# integratedBertha.net
KiCad netlist of a schematic drawn in EAGLE
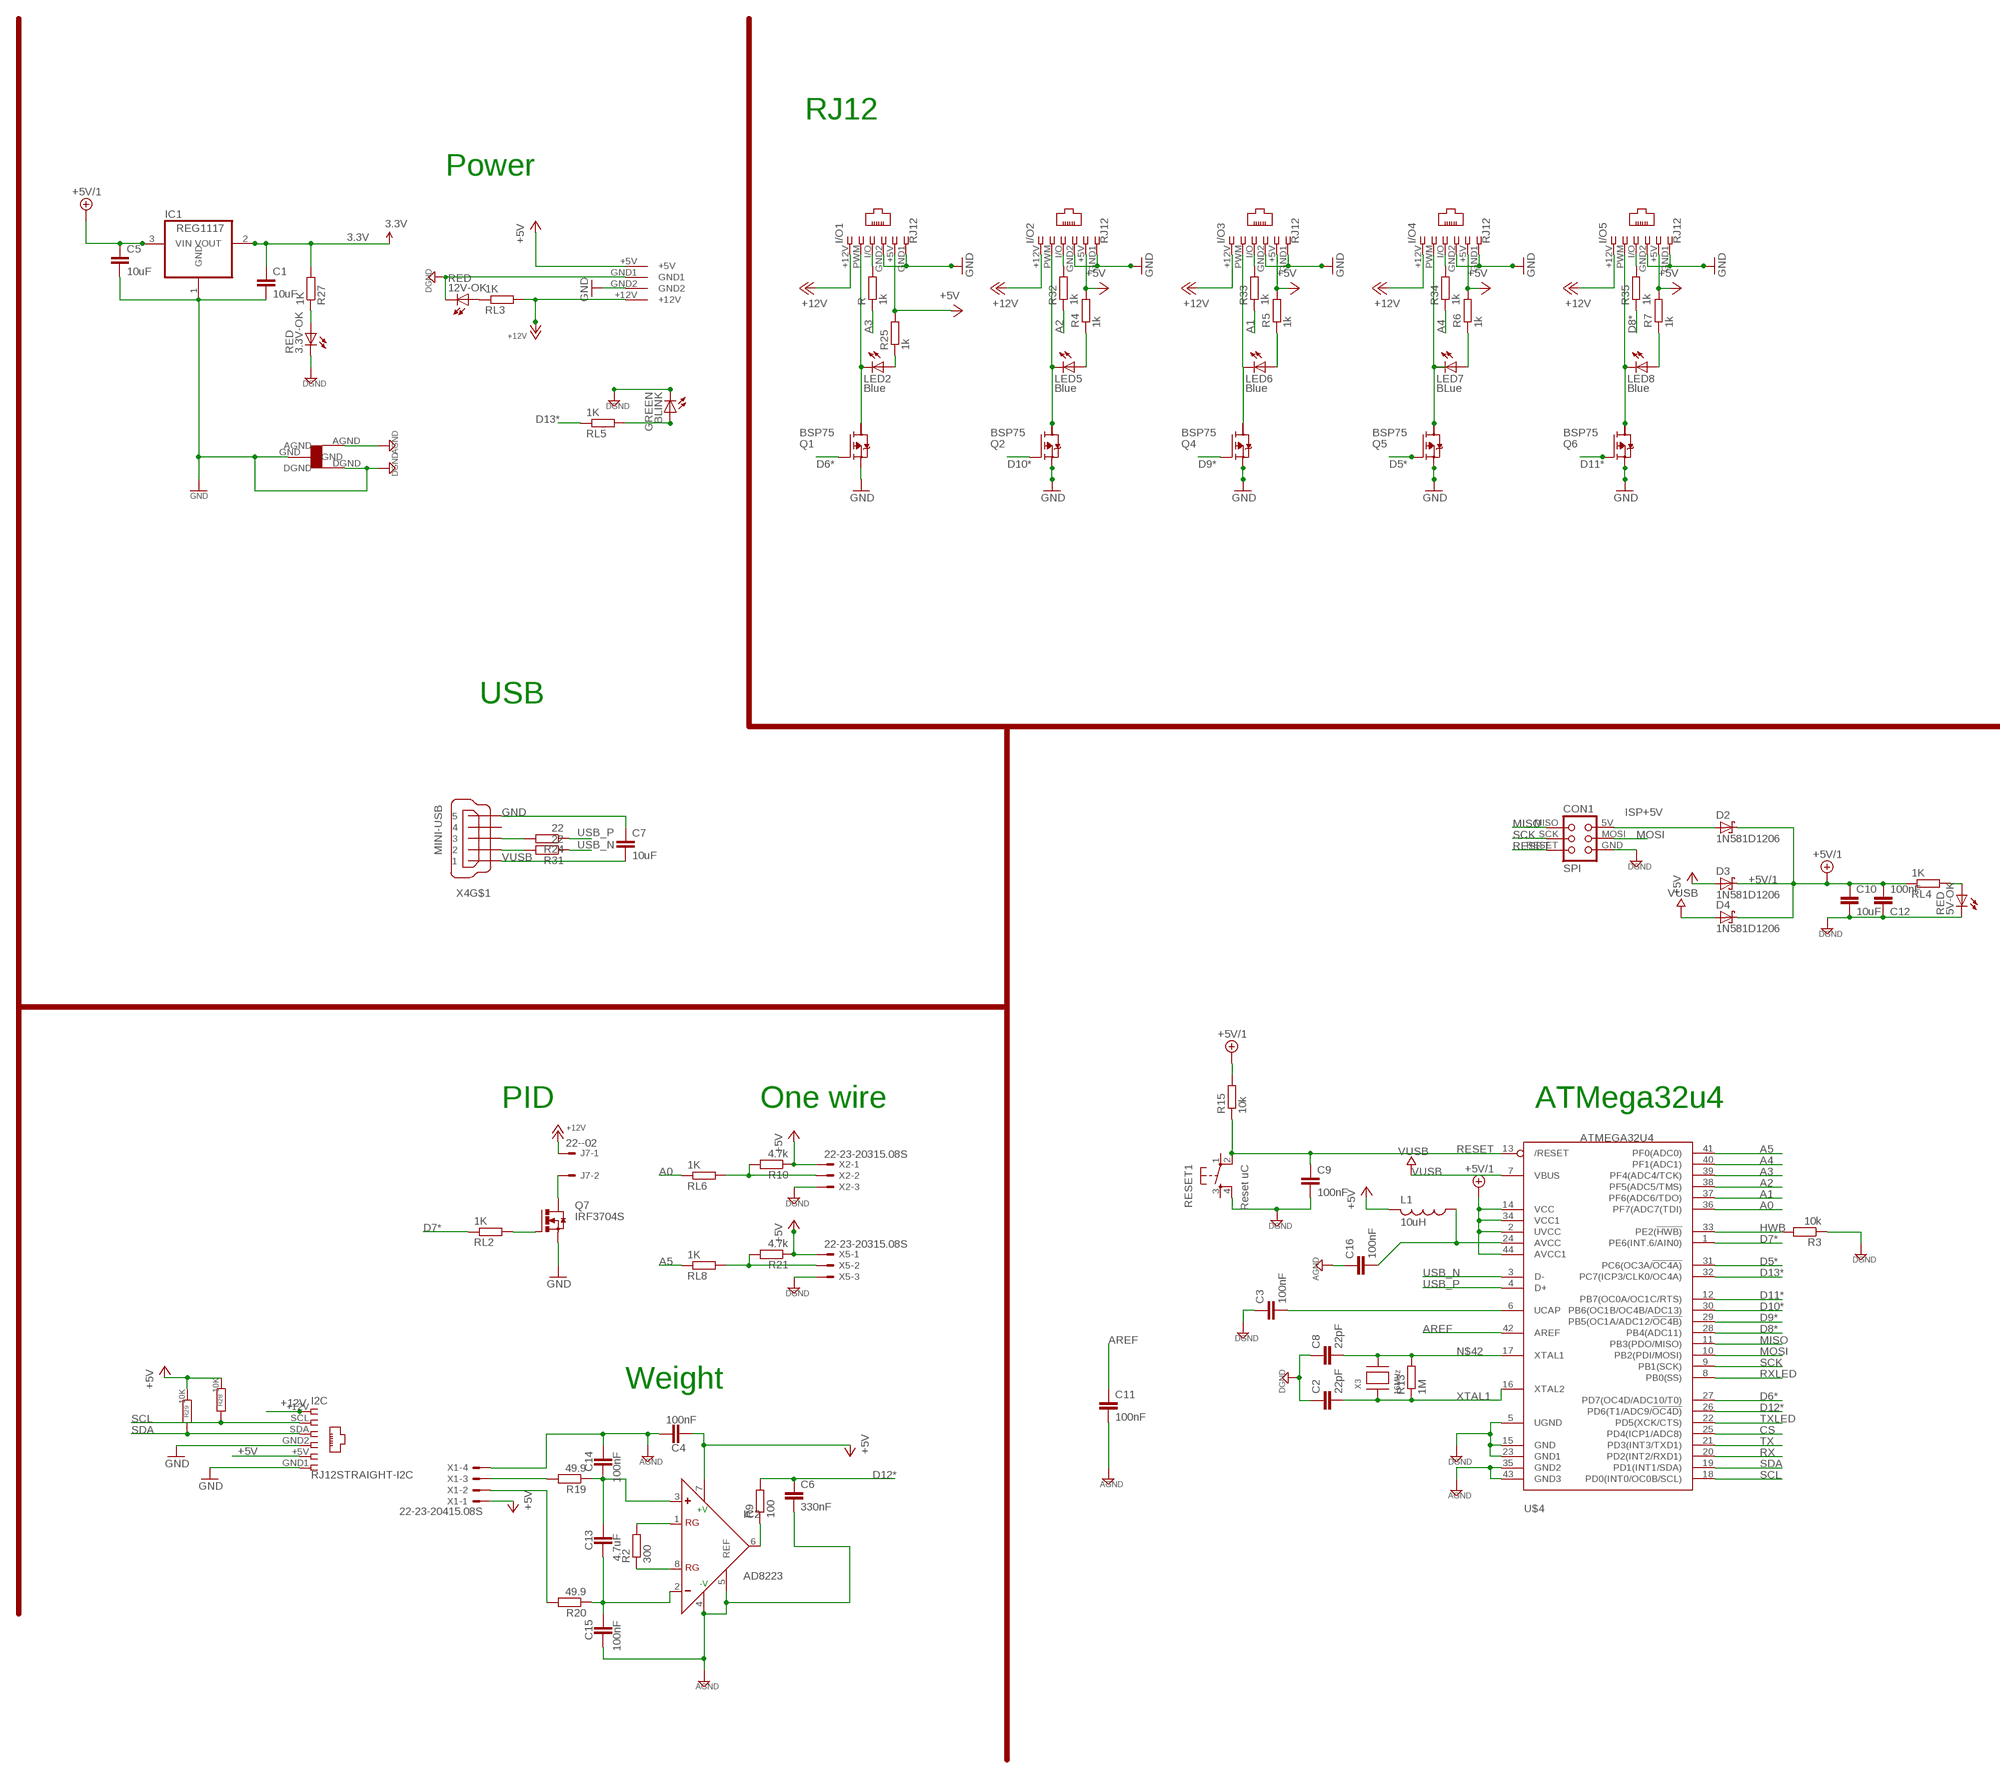
[diagram p0: schematic, sheet 1, part 1 of 2]
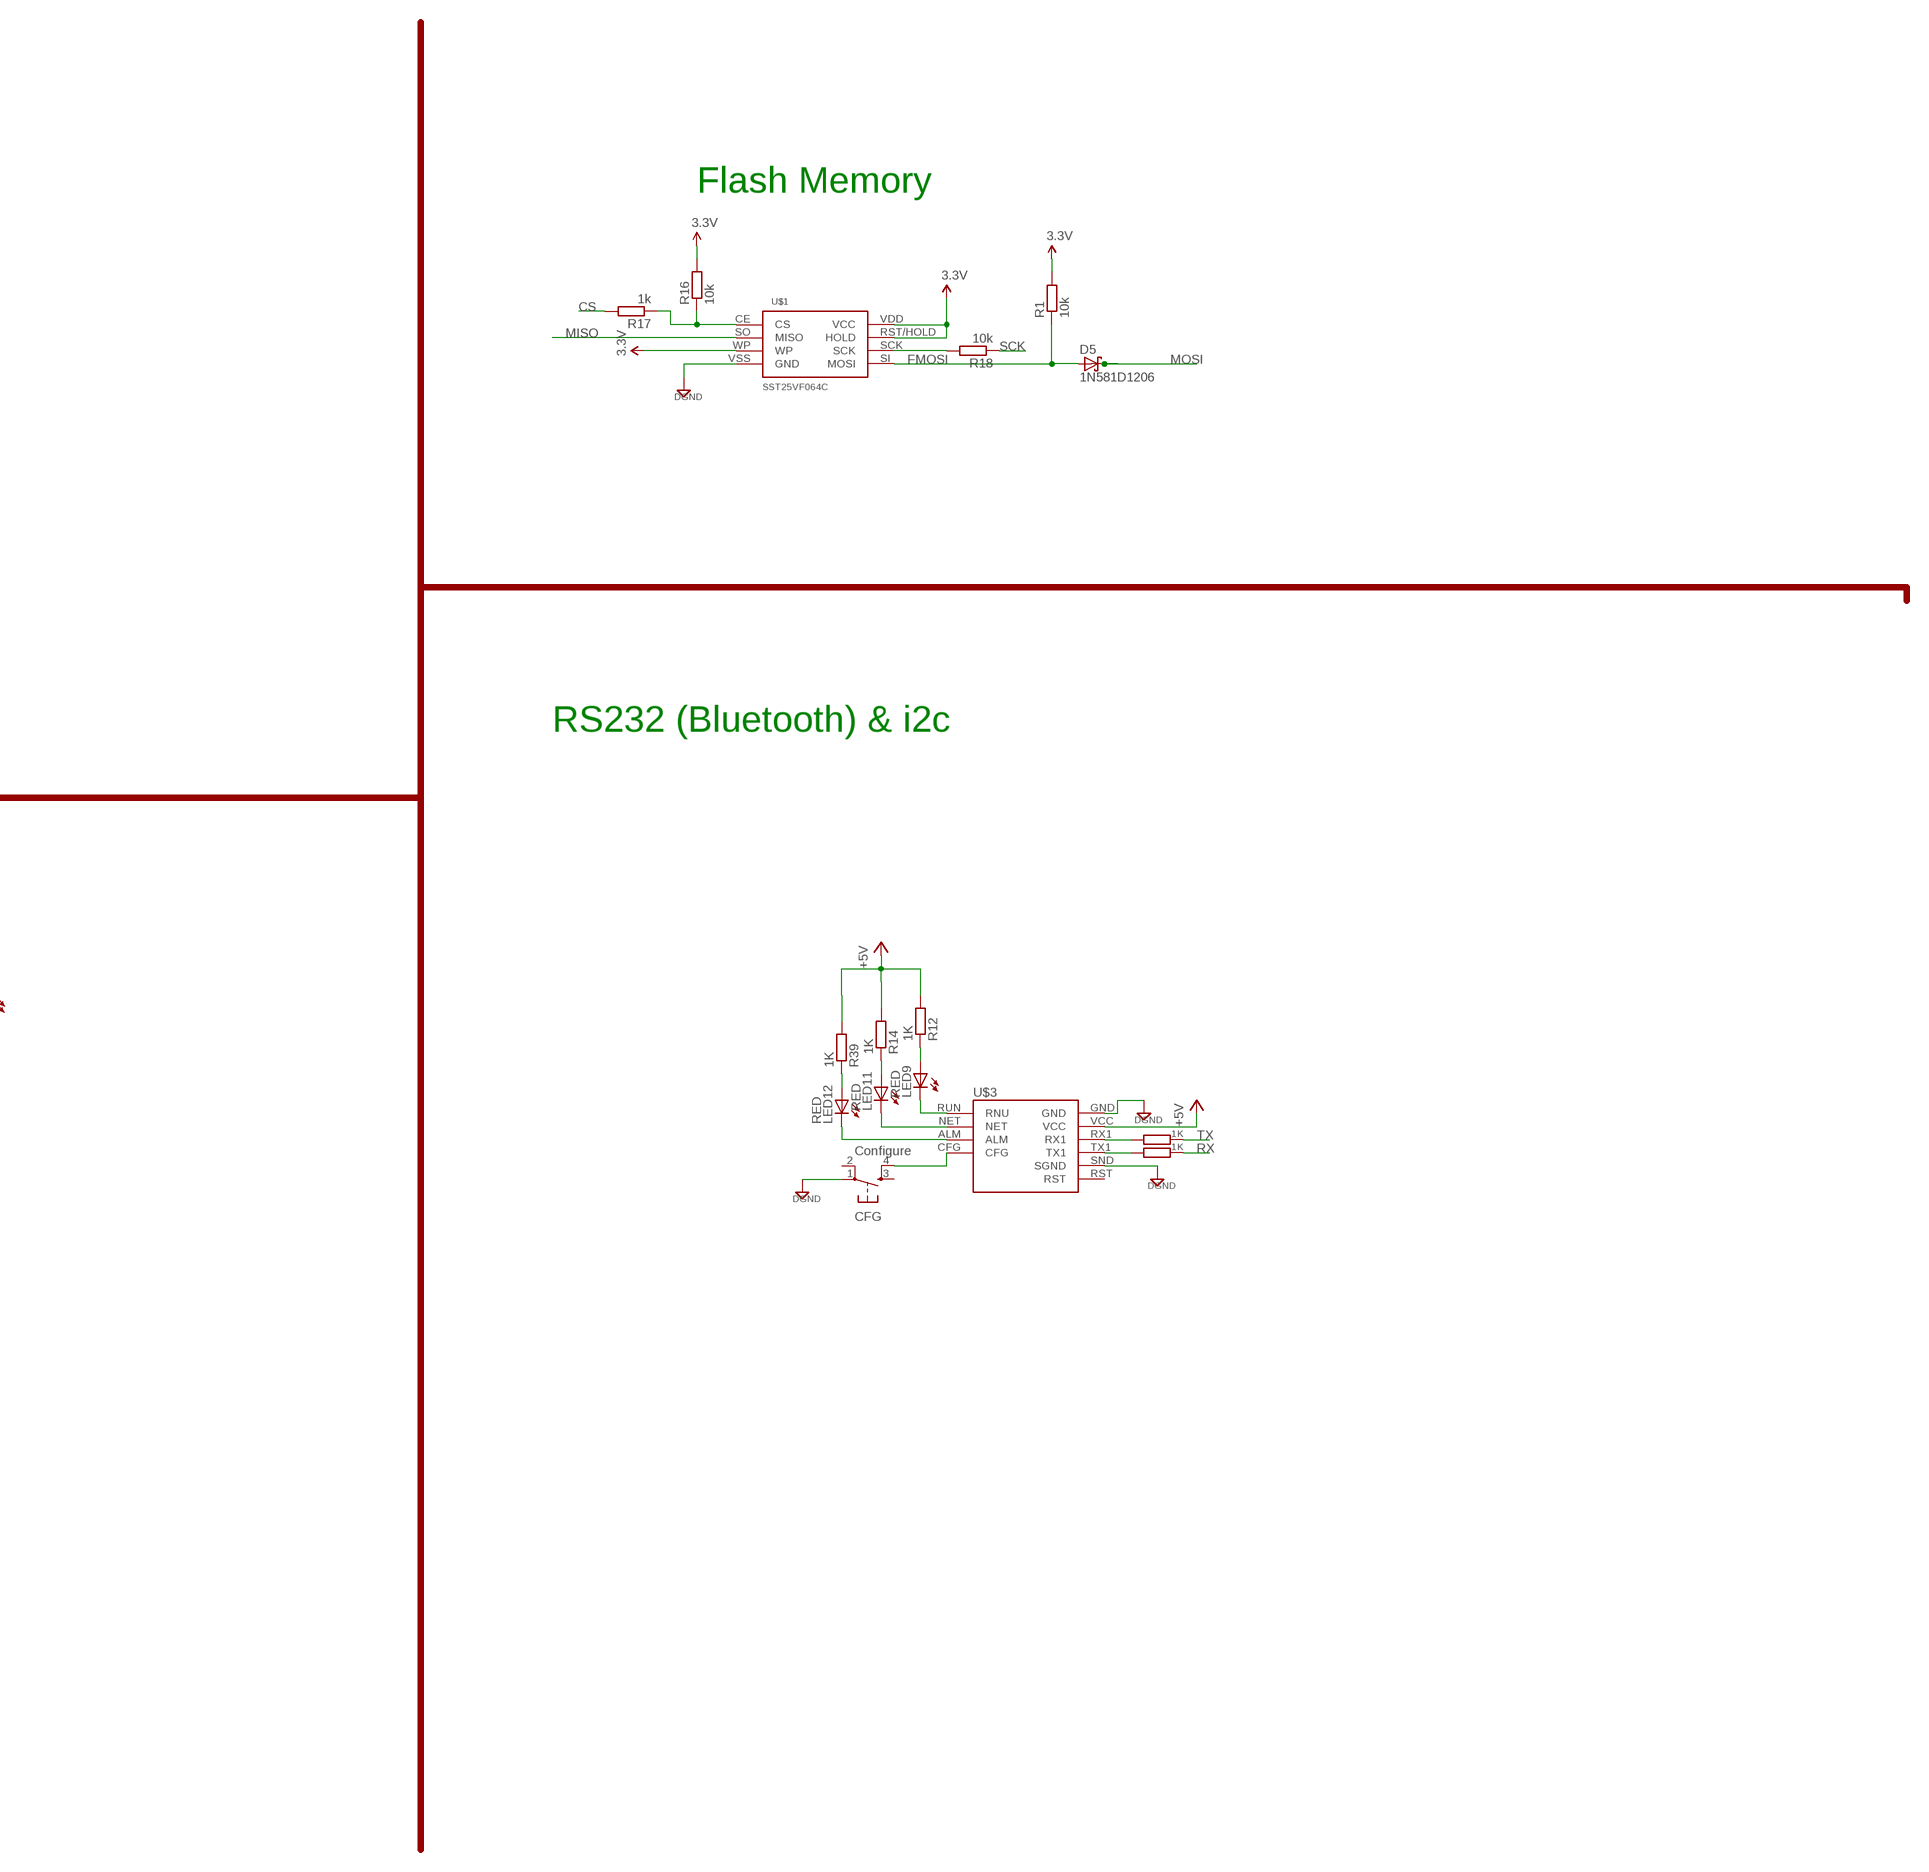
[diagram p1: schematic, sheet 1, part 2 of 2]

(export (version "E")
  (design (tool "Eeschema 10.0.6"))
  (components
    (comp (ref "3.3V-OK")
      (value "RED")
      (footprint "eagle-import:CHIPLED_1206")
      (libsource (lib "eagle-import") (part "LEDCHIPLED_1206"))
    )
    (comp (ref "5V-OK")
      (value "RED")
      (footprint "eagle-import:CHIPLED_1206")
      (libsource (lib "eagle-import") (part "LEDCHIPLED_1206"))
    )
    (comp (ref "12V-OK")
      (value "RED")
      (footprint "eagle-import:CHIPLED_1206")
      (libsource (lib "eagle-import") (part "LEDCHIPLED_1206"))
    )
    (comp (ref "BLINK")
      (value "GREEN")
      (footprint "eagle-import:CHIPLED_1206")
      (libsource (lib "eagle-import") (part "LEDCHIPLED_1206"))
    )
    (comp (ref "C1")
      (value "10uF")
      (footprint "eagle-import:C1206")
      (libsource (lib "eagle-import") (part "C-EUC1206"))
    )
    (comp (ref "C2")
      (value "22pF")
      (footprint "eagle-import:C1206")
      (libsource (lib "eagle-import") (part "C-EUC1206"))
    )
    (comp (ref "C3")
      (value "100nF")
      (footprint "eagle-import:C1206")
      (libsource (lib "eagle-import") (part "C-EUC1206"))
    )
    (comp (ref "C4")
      (value "100nF")
      (footprint "eagle-import:C1206")
      (libsource (lib "eagle-import") (part "C-EUC1206"))
    )
    (comp (ref "C5")
      (value "10uF")
      (footprint "eagle-import:C1206")
      (libsource (lib "eagle-import") (part "C-EUC1206"))
    )
    (comp (ref "C6")
      (value "330nF")
      (footprint "eagle-import:C1206")
      (libsource (lib "eagle-import") (part "C-EUC1206"))
    )
    (comp (ref "C7")
      (value "10uF")
      (footprint "eagle-import:C1206")
      (libsource (lib "eagle-import") (part "C-EUC1206"))
    )
    (comp (ref "C8")
      (value "22pF")
      (footprint "eagle-import:C1206")
      (libsource (lib "eagle-import") (part "C-EUC1206"))
    )
    (comp (ref "C9")
      (value "100nF")
      (footprint "eagle-import:C1206")
      (libsource (lib "eagle-import") (part "C-EUC1206"))
    )
    (comp (ref "C10")
      (value "10uF")
      (footprint "eagle-import:C1206")
      (libsource (lib "eagle-import") (part "C-EUC1206"))
    )
    (comp (ref "C11")
      (value "100nF")
      (footprint "eagle-import:C1206")
      (libsource (lib "eagle-import") (part "C-EUC1206"))
    )
    (comp (ref "C12")
      (value "100nF")
      (footprint "eagle-import:C1206")
      (libsource (lib "eagle-import") (part "C-EUC1206"))
    )
    (comp (ref "C13")
      (value "4.7uF")
      (footprint "eagle-import:C1206")
      (libsource (lib "eagle-import") (part "C-EUC1206"))
    )
    (comp (ref "C14")
      (value "100nF")
      (footprint "eagle-import:C1206")
      (libsource (lib "eagle-import") (part "C-EUC1206"))
    )
    (comp (ref "C15")
      (value "100nF")
      (footprint "eagle-import:C1206")
      (libsource (lib "eagle-import") (part "C-EUC1206"))
    )
    (comp (ref "C16")
      (value "100nF")
      (footprint "eagle-import:C1206")
      (libsource (lib "eagle-import") (part "C-EUC1206"))
    )
    (comp (ref "CFG")
      (value "Configure")
      (footprint "eagle-import:TACTILE_SWITCH_SMD")
      (libsource (lib "eagle-import") (part "TAC_SWITCHSMD"))
    )
    (comp (ref "CON1")
      (value "SPI")
      (footprint "eagle-import:TC2030-MCP-NL")
      (libsource (lib "eagle-import") (part "TINYISPT"))
    )
    (comp (ref "D2")
      (value "1N581D1206")
      (footprint "eagle-import:LED-1206")
      (libsource (lib "eagle-import") (part "1N581D1206"))
    )
    (comp (ref "D3")
      (value "1N581D1206")
      (footprint "eagle-import:LED-1206")
      (libsource (lib "eagle-import") (part "1N581D1206"))
    )
    (comp (ref "D4")
      (value "1N581D1206")
      (footprint "eagle-import:LED-1206")
      (libsource (lib "eagle-import") (part "1N581D1206"))
    )
    (comp (ref "D5")
      (value "1N581D1206")
      (footprint "eagle-import:LED-1206")
      (libsource (lib "eagle-import") (part "1N581D1206"))
    )
    (comp (ref "I/O1")
      (value "RJ12")
      (footprint "eagle-import:RJ12-STRAIGHT")
      (libsource (lib "eagle-import") (part "RJ12STRAIGHT"))
    )
    (comp (ref "I/O2")
      (value "RJ12")
      (footprint "eagle-import:RJ12-STRAIGHT")
      (libsource (lib "eagle-import") (part "RJ12STRAIGHT"))
    )
    (comp (ref "I/O3")
      (value "RJ12")
      (footprint "eagle-import:RJ12-STRAIGHT")
      (libsource (lib "eagle-import") (part "RJ12STRAIGHT"))
    )
    (comp (ref "I/O4")
      (value "RJ12")
      (footprint "eagle-import:RJ12-STRAIGHT")
      (libsource (lib "eagle-import") (part "RJ12STRAIGHT"))
    )
    (comp (ref "I/O5")
      (value "RJ12")
      (footprint "eagle-import:RJ12-STRAIGHT")
      (libsource (lib "eagle-import") (part "RJ12STRAIGHT"))
    )
    (comp (ref "I2C")
      (value "RJ12STRAIGHT-I2C")
      (footprint "eagle-import:RJ12-STRAIGHT-I2C")
      (libsource (lib "eagle-import") (part "RJ12STRAIGHT-I2C"))
    )
    (comp (ref "IC1")
      (value "REG1117")
      (footprint "eagle-import:SOT223")
      (libsource (lib "eagle-import") (part "REG1117"))
    )
    (comp (ref "IC2")
      (value "AD8223")
      (footprint "eagle-import:SO8")
      (fields (field (name "MPN") "AD620AR"))
      (libsource (lib "eagle-import") (part "AD620R"))
    )
    (comp (ref "J7")
      (value "22--02")
      (footprint "eagle-import:2-PIN-5.08S")
      (libsource (lib "eagle-import") (part "22-?-02"))
    )
    (comp (ref "L1")
      (value "10uH")
      (footprint "eagle-import:L2012C")
      (libsource (lib "eagle-import") (part "L-USL2012C"))
    )
    (comp (ref "LED2")
      (value "Blue")
      (footprint "eagle-import:CHIPLED_1206")
      (libsource (lib "eagle-import") (part "LEDCHIPLED_1206"))
    )
    (comp (ref "LED5")
      (value "Blue")
      (footprint "eagle-import:CHIPLED_1206")
      (libsource (lib "eagle-import") (part "LEDCHIPLED_1206"))
    )
    (comp (ref "LED6")
      (value "Blue")
      (footprint "eagle-import:CHIPLED_1206")
      (libsource (lib "eagle-import") (part "LEDCHIPLED_1206"))
    )
    (comp (ref "LED7")
      (value "BLue")
      (footprint "eagle-import:CHIPLED_1206")
      (libsource (lib "eagle-import") (part "LEDCHIPLED_1206"))
    )
    (comp (ref "LED8")
      (value "Blue")
      (footprint "eagle-import:CHIPLED_1206")
      (libsource (lib "eagle-import") (part "LEDCHIPLED_1206"))
    )
    (comp (ref "LED9")
      (value "RED")
      (footprint "eagle-import:CHIPLED_1206")
      (libsource (lib "eagle-import") (part "LEDCHIPLED_1206"))
    )
    (comp (ref "LED11")
      (value "RED")
      (footprint "eagle-import:CHIPLED_1206")
      (libsource (lib "eagle-import") (part "LEDCHIPLED_1206"))
    )
    (comp (ref "LED12")
      (value "RED")
      (footprint "eagle-import:CHIPLED_1206")
      (libsource (lib "eagle-import") (part "LEDCHIPLED_1206"))
    )
    (comp (ref "Q1")
      (value "BSP75")
      (footprint "eagle-import:PG-SOT-223")
      (libsource (lib "eagle-import") (part "BSP613P"))
    )
    (comp (ref "Q2")
      (value "BSP75")
      (footprint "eagle-import:PG-SOT-223")
      (libsource (lib "eagle-import") (part "BSP613P"))
    )
    (comp (ref "Q4")
      (value "BSP75")
      (footprint "eagle-import:PG-SOT-223")
      (libsource (lib "eagle-import") (part "BSP613P"))
    )
    (comp (ref "Q5")
      (value "BSP75")
      (footprint "eagle-import:PG-SOT-223")
      (libsource (lib "eagle-import") (part "BSP613P"))
    )
    (comp (ref "Q6")
      (value "BSP75")
      (footprint "eagle-import:PG-SOT-223")
      (libsource (lib "eagle-import") (part "BSP613P"))
    )
    (comp (ref "Q7")
      (value "IRF3704S")
      (footprint "eagle-import:D2PACK")
      (libsource (lib "eagle-import") (part "IRF3704S"))
    )
    (comp (ref "R")
      (value "1k")
      (footprint "eagle-import:R0805")
      (libsource (lib "eagle-import") (part "R-EU_R0805"))
    )
    (comp (ref "R1")
      (value "10k")
      (footprint "eagle-import:R0805")
      (libsource (lib "eagle-import") (part "R-EU_R0805"))
    )
    (comp (ref "R2")
      (value "300")
      (footprint "eagle-import:R1206")
      (libsource (lib "eagle-import") (part "resistor_R-EU_R1206"))
    )
    (comp (ref "R3")
      (value "10k")
      (footprint "eagle-import:M0805")
      (libsource (lib "eagle-import") (part "resistor_R-EU_M0805"))
    )
    (comp (ref "R4")
      (value "1k")
      (footprint "eagle-import:R0805")
      (libsource (lib "eagle-import") (part "R-EU_R0805"))
    )
    (comp (ref "R5")
      (value "1k")
      (footprint "eagle-import:R0805")
      (libsource (lib "eagle-import") (part "R-EU_R0805"))
    )
    (comp (ref "R6")
      (value "1k")
      (footprint "eagle-import:R0805")
      (libsource (lib "eagle-import") (part "R-EU_R0805"))
    )
    (comp (ref "R7")
      (value "1k")
      (footprint "eagle-import:R0805")
      (libsource (lib "eagle-import") (part "R-EU_R0805"))
    )
    (comp (ref "R8")
      (value "1K")
      (footprint "eagle-import:R0805")
      (libsource (lib "eagle-import") (part "R-EU_R0805"))
    )
    (comp (ref "R9")
      (value "100")
      (footprint "eagle-import:R1206")
      (libsource (lib "eagle-import") (part "resistor_R-EU_R1206"))
    )
    (comp (ref "R10")
      (value "4.7k")
      (footprint "eagle-import:R1206")
      (libsource (lib "eagle-import") (part "resistor_R-EU_R1206"))
    )
    (comp (ref "R11")
      (value "1K")
      (footprint "eagle-import:R0805")
      (libsource (lib "eagle-import") (part "R-EU_R0805"))
    )
    (comp (ref "R12")
      (value "1K")
      (footprint "eagle-import:R0805")
      (libsource (lib "eagle-import") (part "R-EU_R0805"))
    )
    (comp (ref "R13")
      (value "1M")
      (footprint "eagle-import:R1206")
      (libsource (lib "eagle-import") (part "R-EU_R1206"))
    )
    (comp (ref "R14")
      (value "1K")
      (footprint "eagle-import:R0805")
      (libsource (lib "eagle-import") (part "R-EU_R0805"))
    )
    (comp (ref "R15")
      (value "10k")
      (footprint "eagle-import:M0805")
      (libsource (lib "eagle-import") (part "resistor_R-EU_M0805"))
    )
    (comp (ref "R16")
      (value "10k")
      (footprint "eagle-import:R0805")
      (libsource (lib "eagle-import") (part "R-EU_R0805"))
    )
    (comp (ref "R17")
      (value "1k")
      (footprint "eagle-import:R0805")
      (libsource (lib "eagle-import") (part "R-EU_R0805"))
    )
    (comp (ref "R18")
      (value "10k")
      (footprint "eagle-import:R0805")
      (libsource (lib "eagle-import") (part "R-EU_R0805"))
    )
    (comp (ref "R19")
      (value "49.9")
      (footprint "eagle-import:R1206")
      (libsource (lib "eagle-import") (part "resistor_R-EU_R1206"))
    )
    (comp (ref "R20")
      (value "49.9")
      (footprint "eagle-import:R1206")
      (libsource (lib "eagle-import") (part "resistor_R-EU_R1206"))
    )
    (comp (ref "R21")
      (value "4.7k")
      (footprint "eagle-import:R1206")
      (libsource (lib "eagle-import") (part "resistor_R-EU_R1206"))
    )
    (comp (ref "R24")
      (value "22")
      (footprint "eagle-import:M1206")
      (libsource (lib "eagle-import") (part "resistor_R-EU_M1206"))
    )
    (comp (ref "R25")
      (value "1k")
      (footprint "eagle-import:R0805")
      (libsource (lib "eagle-import") (part "R-EU_R0805"))
    )
    (comp (ref "R27")
      (value "1K")
      (footprint "eagle-import:R0805")
      (libsource (lib "eagle-import") (part "R-EU_R0805"))
    )
    (comp (ref "R28")
      (value "10K")
      (footprint "eagle-import:M0805")
      (libsource (lib "eagle-import") (part "resistor_R-EU_M0805"))
    )
    (comp (ref "R29")
      (value "10K")
      (footprint "eagle-import:M0805")
      (libsource (lib "eagle-import") (part "resistor_R-EU_M0805"))
    )
    (comp (ref "R31")
      (value "22")
      (footprint "eagle-import:M1206")
      (libsource (lib "eagle-import") (part "resistor_R-EU_M1206"))
    )
    (comp (ref "R32")
      (value "1k")
      (footprint "eagle-import:R0805")
      (libsource (lib "eagle-import") (part "R-EU_R0805"))
    )
    (comp (ref "R33")
      (value "1k")
      (footprint "eagle-import:R0805")
      (libsource (lib "eagle-import") (part "R-EU_R0805"))
    )
    (comp (ref "R34")
      (value "1k")
      (footprint "eagle-import:R0805")
      (libsource (lib "eagle-import") (part "R-EU_R0805"))
    )
    (comp (ref "R35")
      (value "1k")
      (footprint "eagle-import:R0805")
      (libsource (lib "eagle-import") (part "R-EU_R0805"))
    )
    (comp (ref "R39")
      (value "1K")
      (footprint "eagle-import:R0805")
      (libsource (lib "eagle-import") (part "R-EU_R0805"))
    )
    (comp (ref "RESET1")
      (value "Reset uC")
      (footprint "eagle-import:TACTILE_SWITCH_SMD")
      (libsource (lib "eagle-import") (part "TAC_SWITCHSMD"))
    )
    (comp (ref "RL2")
      (value "1K")
      (footprint "eagle-import:R0805")
      (libsource (lib "eagle-import") (part "R-EU_R0805"))
    )
    (comp (ref "RL3")
      (value "1K")
      (footprint "eagle-import:R0805")
      (libsource (lib "eagle-import") (part "R-EU_R0805"))
    )
    (comp (ref "RL4")
      (value "1K")
      (footprint "eagle-import:R0805")
      (libsource (lib "eagle-import") (part "resistor_R-EU_R0805"))
    )
    (comp (ref "RL5")
      (value "1K")
      (footprint "eagle-import:R0805")
      (libsource (lib "eagle-import") (part "R-EU_R0805"))
    )
    (comp (ref "RL6")
      (value "1K")
      (footprint "eagle-import:R0805")
      (libsource (lib "eagle-import") (part "R-EU_R0805"))
    )
    (comp (ref "RL8")
      (value "1K")
      (footprint "eagle-import:R0805")
      (libsource (lib "eagle-import") (part "R-EU_R0805"))
    )
    (comp (ref "U$1")
      (value "SST25VF064C")
      (footprint "eagle-import:SOIC_8-LEAD")
      (libsource (lib "eagle-import") (part "SST25VF064C"))
    )
    (comp (ref "U$2")
      (value "STARGND")
      (footprint "eagle-import:STAR")
      (libsource (lib "eagle-import") (part "STARGND"))
    )
    (comp (ref "U$3")
      (value "SZ05-ZIGBEE")
      (footprint "eagle-import:SZ05-ZIGBEE4")
      (libsource (lib "eagle-import") (part "SZ05-ZIGBEETHROUGHHOLE"))
    )
    (comp (ref "U$4")
      (value "ATMEGA32U4")
      (footprint "eagle-import:TQFP44")
      (libsource (lib "eagle-import") (part "ATMEGA32U4-AU"))
    )
    (comp (ref "U$6")
      (value "KPJX-4S-S")
      (footprint "eagle-import:KPJX-4S-S")
      (libsource (lib "eagle-import") (part "KPJX-4S-S"))
    )
    (comp (ref "X1")
      (value "22-23-20415.08S")
      (footprint "eagle-import:4-PIN-5.08S")
      (libsource (lib "eagle-import") (part "22-23-20415.08S"))
    )
    (comp (ref "X2")
      (value "22-23-20315.08S")
      (footprint "eagle-import:3-PIN-5.08S")
      (libsource (lib "eagle-import") (part "22-23-20315.08S"))
    )
    (comp (ref "X3")
      (value "16MHz")
      (footprint "eagle-import:NX6035")
      (libsource (lib "eagle-import") (part "XTALNX6035"))
    )
    (comp (ref "X4")
      (value "MINI-USB")
      (footprint "eagle-import:32005-201")
      (libsource (lib "eagle-import") (part "MINI-USB-SCHIELD-32005-201"))
    )
    (comp (ref "X5")
      (value "22-23-20315.08S")
      (footprint "eagle-import:3-PIN-5.08S")
      (libsource (lib "eagle-import") (part "22-23-20315.08S"))
    )
  )
  (nets
    (net (code "1") (name "+5V") (class "Default")
      (node (ref "C4") (pin "2") (pinfunction "2_2") (pintype "passive"))
      (node (ref "D3") (pin "A") (pinfunction "A_A") (pintype "passive"))
      (node (ref "I/O1") (pin "+5V") (pinfunction "5_+5V") (pintype "bidirectional"))
      (node (ref "I/O2") (pin "+5V") (pinfunction "5_+5V") (pintype "bidirectional"))
      (node (ref "I/O3") (pin "+5V") (pinfunction "5_+5V") (pintype "bidirectional"))
      (node (ref "I/O4") (pin "+5V") (pinfunction "5_+5V") (pintype "bidirectional"))
      (node (ref "I/O5") (pin "+5V") (pinfunction "5_+5V") (pintype "bidirectional"))
      (node (ref "I2C") (pin "+5V") (pinfunction "5_+5V") (pintype "bidirectional"))
      (node (ref "IC2") (pin "7") (pinfunction "+V_7") (pintype "power_in"))
      (node (ref "L1") (pin "2") (pinfunction "2_2") (pintype "passive"))
      (node (ref "R10") (pin "1") (pinfunction "1_1") (pintype "passive"))
      (node (ref "R12") (pin "2") (pinfunction "2_2") (pintype "passive"))
      (node (ref "R14") (pin "2") (pinfunction "2_2") (pintype "passive"))
      (node (ref "R21") (pin "1") (pinfunction "1_1") (pintype "passive"))
      (node (ref "R25") (pin "2") (pinfunction "2_2") (pintype "passive"))
      (node (ref "R28") (pin "1") (pinfunction "1_1") (pintype "passive"))
      (node (ref "R29") (pin "1") (pinfunction "1_1") (pintype "passive"))
      (node (ref "R39") (pin "2") (pinfunction "2_2") (pintype "passive"))
      (node (ref "R4") (pin "2") (pinfunction "2_2") (pintype "passive"))
      (node (ref "R5") (pin "2") (pinfunction "2_2") (pintype "passive"))
      (node (ref "R6") (pin "2") (pinfunction "2_2") (pintype "passive"))
      (node (ref "R7") (pin "2") (pinfunction "2_2") (pintype "passive"))
      (node (ref "U$3") (pin "VCC") (pinfunction "VCC_VCC") (pintype "bidirectional"))
      (node (ref "U$6") (pin "+5V") (pinfunction "+5V_+5V") (pintype "power_in"))
      (node (ref "X1") (pin "1") (pinfunction "S_1") (pintype "passive"))
      (node (ref "X2") (pin "1") (pinfunction "S_1") (pintype "passive"))
      (node (ref "X5") (pin "1") (pinfunction "S_1") (pintype "passive"))
    )
    (net (code "2") (name "+5V{slash}1") (class "Default")
      (node (ref "C10") (pin "1") (pinfunction "1_1") (pintype "passive"))
      (node (ref "C12") (pin "2") (pinfunction "2_2") (pintype "passive"))
      (node (ref "C5") (pin "1") (pinfunction "1_1") (pintype "passive"))
      (node (ref "D2") (pin "C") (pinfunction "C_C") (pintype "passive"))
      (node (ref "D3") (pin "C") (pinfunction "C_C") (pintype "passive"))
      (node (ref "D4") (pin "C") (pinfunction "C_C") (pintype "passive"))
      (node (ref "IC1") (pin "3") (pinfunction "VIN_3") (pintype "input"))
      (node (ref "R15") (pin "2") (pinfunction "2_2") (pintype "passive"))
      (node (ref "RL4") (pin "1") (pinfunction "1_1") (pintype "passive"))
      (node (ref "U$4") (pin "14") (pinfunction "VCC_14") (pintype "bidirectional"))
      (node (ref "U$4") (pin "2") (pinfunction "UVCC_2") (pintype "bidirectional"))
      (node (ref "U$4") (pin "34") (pinfunction "VCC1_34") (pintype "bidirectional"))
      (node (ref "U$4") (pin "44") (pinfunction "AVCC1_44") (pintype "bidirectional"))
    )
    (net (code "3") (name "+12V") (class "Default")
      (node (ref "I/O1") (pin "+12V") (pinfunction "1_+12V") (pintype "bidirectional"))
      (node (ref "I/O2") (pin "+12V") (pinfunction "1_+12V") (pintype "bidirectional"))
      (node (ref "I/O3") (pin "+12V") (pinfunction "1_+12V") (pintype "bidirectional"))
      (node (ref "I/O4") (pin "+12V") (pinfunction "1_+12V") (pintype "bidirectional"))
      (node (ref "I/O5") (pin "+12V") (pinfunction "1_+12V") (pintype "bidirectional"))
      (node (ref "I2C") (pin "+12V") (pinfunction "1_+12V") (pintype "bidirectional"))
      (node (ref "J7") (pin "1") (pinfunction "S_1") (pintype "passive"))
      (node (ref "RL3") (pin "2") (pinfunction "2_2") (pintype "passive"))
      (node (ref "U$6") (pin "+12V") (pinfunction "+12V_+12V") (pintype "power_in"))
    )
    (net (code "4") (name "/A0") (class "Default")
      (node (ref "RL6") (pin "1") (pinfunction "1_1") (pintype "passive"))
      (node (ref "U$4") (pin "36") (pinfunction "PF7(ADC7(TDI)_36") (pintype "bidirectional"))
    )
    (net (code "5") (name "/A1") (class "Default")
      (node (ref "R33") (pin "1") (pinfunction "1_1") (pintype "passive"))
      (node (ref "U$4") (pin "37") (pinfunction "PF6(ADC6/TDO)_37") (pintype "bidirectional"))
    )
    (net (code "6") (name "/A2") (class "Default")
      (node (ref "R32") (pin "1") (pinfunction "1_1") (pintype "passive"))
      (node (ref "U$4") (pin "38") (pinfunction "PF5(ADC5/TMS)_38") (pintype "bidirectional"))
    )
    (net (code "7") (name "/A3") (class "Default")
      (node (ref "R") (pin "1") (pinfunction "1_1") (pintype "passive"))
      (node (ref "U$4") (pin "39") (pinfunction "PF4(ADC4/TCK)_39") (pintype "bidirectional"))
    )
    (net (code "8") (name "/A4") (class "Default")
      (node (ref "R34") (pin "1") (pinfunction "1_1") (pintype "passive"))
      (node (ref "U$4") (pin "40") (pinfunction "PF1(ADC1)_40") (pintype "bidirectional"))
    )
    (net (code "9") (name "/A5") (class "Default")
      (node (ref "RL8") (pin "1") (pinfunction "1_1") (pintype "passive"))
      (node (ref "U$4") (pin "41") (pinfunction "PF0(ADC0)_41") (pintype "bidirectional"))
    )
    (net (code "10") (name "/AREF") (class "Default")
      (node (ref "C11") (pin "1") (pinfunction "1_1") (pintype "passive"))
      (node (ref "U$4") (pin "42") (pinfunction "AREF_42") (pintype "bidirectional"))
    )
    (net (code "11") (name "/CS") (class "Default")
      (node (ref "R17") (pin "2") (pinfunction "2_2") (pintype "passive"))
      (node (ref "U$4") (pin "25") (pinfunction "PD4(ICP1/ADC8)_25") (pintype "bidirectional"))
    )
    (net (code "12") (name "/D5*") (class "Default")
      (node (ref "Q5") (pin "1") (pinfunction "G_1") (pintype "passive"))
      (node (ref "U$4") (pin "31") (pinfunction "PC6(OC3A/~{OC4A})_31") (pintype "bidirectional"))
    )
    (net (code "13") (name "/D6*") (class "Default")
      (node (ref "Q1") (pin "1") (pinfunction "G_1") (pintype "passive"))
      (node (ref "U$4") (pin "27") (pinfunction "PD7(OC4D/ADC10/T0)_27") (pintype "bidirectional"))
    )
    (net (code "14") (name "/D7*") (class "Default")
      (node (ref "RL2") (pin "1") (pinfunction "1_1") (pintype "passive"))
      (node (ref "U$4") (pin "1") (pinfunction "PE6(INT.6/AIN0)_1") (pintype "bidirectional"))
    )
    (net (code "15") (name "/D8*") (class "Default")
      (node (ref "R35") (pin "1") (pinfunction "1_1") (pintype "passive"))
      (node (ref "U$4") (pin "28") (pinfunction "PB4(ADC11)_28") (pintype "bidirectional"))
    )
    (net (code "16") (name "/D9*") (class "Default")
      (node (ref "Q4") (pin "1") (pinfunction "G_1") (pintype "passive"))
      (node (ref "U$4") (pin "29") (pinfunction "PB5(OC1A/ADC12/~{OC4B})_29") (pintype "bidirectional"))
    )
    (net (code "17") (name "/D10*") (class "Default")
      (node (ref "Q2") (pin "1") (pinfunction "G_1") (pintype "passive"))
      (node (ref "U$4") (pin "30") (pinfunction "PB6(OC1B/OC4B/ADC13)_30") (pintype "bidirectional"))
    )
    (net (code "18") (name "/D11*") (class "Default")
      (node (ref "Q6") (pin "1") (pinfunction "G_1") (pintype "passive"))
      (node (ref "U$4") (pin "12") (pinfunction "PB7(OC0A/OC1C/RTS)_12") (pintype "bidirectional"))
    )
    (net (code "19") (name "/D12*") (class "Default")
      (node (ref "C6") (pin "1") (pinfunction "1_1") (pintype "passive"))
      (node (ref "R9") (pin "2") (pinfunction "2_2") (pintype "passive"))
      (node (ref "U$4") (pin "26") (pinfunction "PD6(T1/ADC9/~{OC4D})_26") (pintype "bidirectional"))
    )
    (net (code "20") (name "/D13*") (class "Default")
      (node (ref "RL5") (pin "1") (pinfunction "1_1") (pintype "passive"))
      (node (ref "U$4") (pin "32") (pinfunction "PC7(ICP3/CLK0/OC4A)_32") (pintype "bidirectional"))
    )
    (net (code "21") (name "/FMOSI") (class "Default")
      (node (ref "D5") (pin "A") (pinfunction "A_A") (pintype "passive"))
      (node (ref "R1") (pin "1") (pinfunction "1_1") (pintype "passive"))
      (node (ref "U$1") (pin "SI") (pinfunction "MOSI_SI") (pintype "bidirectional"))
    )
    (net (code "22") (name "/HWB") (class "Default")
      (node (ref "R3") (pin "2") (pinfunction "2_2") (pintype "passive"))
      (node (ref "U$4") (pin "33") (pinfunction "PE2(~{HWB})_33") (pintype "bidirectional"))
    )
    (net (code "23") (name "/ISP+5V") (class "Default")
      (node (ref "CON1") (pin "5V") (pinfunction "VCC_5V") (pintype "passive"))
      (node (ref "D2") (pin "A") (pinfunction "A_A") (pintype "passive"))
    )
    (net (code "24") (name "/MISO") (class "Default")
      (node (ref "CON1") (pin "MISO") (pinfunction "MISO_MISO") (pintype "passive"))
      (node (ref "U$1") (pin "SO") (pinfunction "MISO_SO") (pintype "bidirectional"))
      (node (ref "U$4") (pin "11") (pinfunction "PB3(PDO/MISO)_11") (pintype "bidirectional"))
    )
    (net (code "25") (name "/MOSI") (class "Default")
      (node (ref "CON1") (pin "MOSI") (pinfunction "MOSI_MOSI") (pintype "passive"))
      (node (ref "D5") (pin "C") (pinfunction "C_C") (pintype "passive"))
      (node (ref "U$4") (pin "10") (pinfunction "PB2(PDI/MOSI)_10") (pintype "bidirectional"))
    )
    (net (code "26") (name "/N$42") (class "Default")
      (node (ref "C8") (pin "2") (pinfunction "2_2") (pintype "passive"))
      (node (ref "R13") (pin "2") (pinfunction "2_2") (pintype "passive"))
      (node (ref "U$4") (pin "17") (pinfunction "XTAL1_17") (pintype "bidirectional"))
      (node (ref "X3") (pin "P$2") (pinfunction "P$2_P$2") (pintype "bidirectional"))
    )
    (net (code "27") (name "/RESET") (class "Default")
      (node (ref "C9") (pin "1") (pinfunction "1_1") (pintype "passive"))
      (node (ref "CON1") (pin "RESET") (pinfunction "RESET_RESET") (pintype "passive"))
      (node (ref "R15") (pin "1") (pinfunction "1_1") (pintype "passive"))
      (node (ref "RESET1") (pin "2") (pinfunction "2_2") (pintype "passive"))
      (node (ref "U$4") (pin "13") (pinfunction "/RESET_13") (pintype "bidirectional"))
    )
    (net (code "28") (name "/RX") (class "Default")
      (node (ref "R8") (pin "1") (pinfunction "1_1") (pintype "passive"))
      (node (ref "U$4") (pin "20") (pinfunction "PD2(INT2/RXD1)_20") (pintype "bidirectional"))
    )
    (net (code "29") (name "/RXLED") (class "Default")
      (node (ref "U$4") (pin "8") (pinfunction "PB0(SS)_8") (pintype "bidirectional"))
    )
    (net (code "30") (name "/SCK") (class "Default")
      (node (ref "CON1") (pin "SCK") (pinfunction "SCK_SCK") (pintype "passive"))
      (node (ref "R18") (pin "1") (pinfunction "1_1") (pintype "passive"))
      (node (ref "U$4") (pin "9") (pinfunction "PB1(SCK)_9") (pintype "bidirectional"))
    )
    (net (code "31") (name "/SCL") (class "Default")
      (node (ref "I2C") (pin "SCL") (pinfunction "2_SCL") (pintype "bidirectional"))
      (node (ref "R28") (pin "2") (pinfunction "2_2") (pintype "passive"))
      (node (ref "U$4") (pin "18") (pinfunction "PD0(INT0/OC0B/SCL)_18") (pintype "bidirectional"))
    )
    (net (code "32") (name "/SDA") (class "Default")
      (node (ref "I2C") (pin "SDA") (pinfunction "3_SDA") (pintype "bidirectional"))
      (node (ref "R29") (pin "2") (pinfunction "2_2") (pintype "passive"))
      (node (ref "U$4") (pin "19") (pinfunction "PD1(INT1/SDA)_19") (pintype "bidirectional"))
    )
    (net (code "33") (name "/TX") (class "Default")
      (node (ref "R11") (pin "1") (pinfunction "1_1") (pintype "passive"))
      (node (ref "U$4") (pin "21") (pinfunction "PD3(INT3/TXD1)_21") (pintype "bidirectional"))
    )
    (net (code "34") (name "/TXLED") (class "Default")
      (node (ref "U$4") (pin "22") (pinfunction "PD5(XCK/CTS)_22") (pintype "bidirectional"))
    )
    (net (code "35") (name "/USB_N") (class "Default")
      (node (ref "R31") (pin "1") (pinfunction "1_1") (pintype "passive"))
      (node (ref "U$4") (pin "3") (pinfunction "D-_3") (pintype "bidirectional"))
    )
    (net (code "36") (name "/USB_P") (class "Default")
      (node (ref "R24") (pin "1") (pinfunction "1_1") (pintype "passive"))
      (node (ref "U$4") (pin "4") (pinfunction "D+_4") (pintype "bidirectional"))
    )
    (net (code "37") (name "/XTAL1") (class "Default")
      (node (ref "C2") (pin "2") (pinfunction "2_2") (pintype "passive"))
      (node (ref "R13") (pin "1") (pinfunction "1_1") (pintype "passive"))
      (node (ref "U$4") (pin "16") (pinfunction "XTAL2_16") (pintype "bidirectional"))
      (node (ref "X3") (pin "P$1") (pinfunction "P$1_P$1") (pintype "bidirectional"))
    )
    (net (code "38") (name "3.3V") (class "Default")
      (node (ref "C1") (pin "1") (pinfunction "1_1") (pintype "passive"))
      (node (ref "IC1") (pin "2") (pinfunction "VOUT_2") (pintype "output"))
      (node (ref "R1") (pin "2") (pinfunction "2_2") (pintype "passive"))
      (node (ref "R16") (pin "2") (pinfunction "2_2") (pintype "passive"))
      (node (ref "R27") (pin "2") (pinfunction "2_2") (pintype "passive"))
      (node (ref "U$1") (pin "RST/HOLD") (pinfunction "HOLD_RST/HOLD") (pintype "bidirectional"))
      (node (ref "U$1") (pin "VDD") (pinfunction "VCC_VDD") (pintype "bidirectional"))
      (node (ref "U$1") (pin "WP") (pinfunction "WP_WP") (pintype "bidirectional"))
    )
    (net (code "39") (name "AGND") (class "Default")
      (node (ref "C11") (pin "2") (pinfunction "2_2") (pintype "passive"))
      (node (ref "C14") (pin "1") (pinfunction "1_1") (pintype "passive"))
      (node (ref "C15") (pin "2") (pinfunction "2_2") (pintype "passive"))
      (node (ref "C16") (pin "1") (pinfunction "1_1") (pintype "passive"))
      (node (ref "C4") (pin "1") (pinfunction "1_1") (pintype "passive"))
      (node (ref "C6") (pin "2") (pinfunction "2_2") (pintype "passive"))
      (node (ref "IC2") (pin "4") (pinfunction "-V_4") (pintype "power_in"))
      (node (ref "IC2") (pin "5") (pinfunction "REF_5") (pintype "passive"))
      (node (ref "U$2") (pin "AGND") (pinfunction "AGND_AGND") (pintype "output"))
      (node (ref "U$4") (pin "35") (pinfunction "GND2_35") (pintype "bidirectional"))
      (node (ref "U$4") (pin "43") (pinfunction "GND3_43") (pintype "bidirectional"))
      (node (ref "X1") (pin "4") (pinfunction "S_4") (pintype "passive"))
    )
    (net (code "40") (name "DGND") (class "Default")
      (node (ref "12V-OK") (pin "C") (pinfunction "C_C") (pintype "passive"))
      (node (ref "3.3V-OK") (pin "C") (pinfunction "C_C") (pintype "passive"))
      (node (ref "5V-OK") (pin "C") (pinfunction "C_C") (pintype "passive"))
      (node (ref "BLINK") (pin "C") (pinfunction "C_C") (pintype "passive"))
      (node (ref "C1") (pin "2") (pinfunction "2_2") (pintype "passive"))
      (node (ref "C10") (pin "2") (pinfunction "2_2") (pintype "passive"))
      (node (ref "C12") (pin "1") (pinfunction "1_1") (pintype "passive"))
      (node (ref "C2") (pin "1") (pinfunction "1_1") (pintype "passive"))
      (node (ref "C3") (pin "1") (pinfunction "1_1") (pintype "passive"))
      (node (ref "C5") (pin "2") (pinfunction "2_2") (pintype "passive"))
      (node (ref "C7") (pin "1") (pinfunction "1_1") (pintype "passive"))
      (node (ref "C8") (pin "1") (pinfunction "1_1") (pintype "passive"))
      (node (ref "C9") (pin "2") (pinfunction "2_2") (pintype "passive"))
      (node (ref "CFG") (pin "1") (pinfunction "1_1") (pintype "passive"))
      (node (ref "CON1") (pin "GND") (pinfunction "GND_GND") (pintype "passive"))
      (node (ref "I/O1") (pin "GND1") (pinfunction "6_GND1") (pintype "bidirectional"))
      (node (ref "I/O1") (pin "GND2") (pinfunction "4_GND2") (pintype "bidirectional"))
      (node (ref "I/O2") (pin "GND1") (pinfunction "6_GND1") (pintype "bidirectional"))
      (node (ref "I/O2") (pin "GND2") (pinfunction "4_GND2") (pintype "bidirectional"))
      (node (ref "I/O3") (pin "GND1") (pinfunction "6_GND1") (pintype "bidirectional"))
      (node (ref "I/O3") (pin "GND2") (pinfunction "4_GND2") (pintype "bidirectional"))
      (node (ref "I/O4") (pin "GND1") (pinfunction "6_GND1") (pintype "bidirectional"))
      (node (ref "I/O4") (pin "GND2") (pinfunction "4_GND2") (pintype "bidirectional"))
      (node (ref "I/O5") (pin "GND1") (pinfunction "6_GND1") (pintype "bidirectional"))
      (node (ref "I/O5") (pin "GND2") (pinfunction "4_GND2") (pintype "bidirectional"))
      (node (ref "I2C") (pin "GND1") (pinfunction "6_GND1") (pintype "bidirectional"))
      (node (ref "I2C") (pin "GND2") (pinfunction "4_GND2") (pintype "bidirectional"))
      (node (ref "IC1") (pin "1") (pinfunction "GND_1") (pintype "power_in"))
      (node (ref "Q1") (pin "3") (pinfunction "S_3") (pintype "passive"))
      (node (ref "Q2") (pin "3") (pinfunction "S_3") (pintype "passive"))
      (node (ref "Q4") (pin "3") (pinfunction "S_3") (pintype "passive"))
      (node (ref "Q5") (pin "3") (pinfunction "S_3") (pintype "passive"))
      (node (ref "Q6") (pin "3") (pinfunction "S_3") (pintype "passive"))
      (node (ref "Q7") (pin "3") (pinfunction "S_3") (pintype "passive"))
      (node (ref "R3") (pin "1") (pinfunction "1_1") (pintype "passive"))
      (node (ref "RESET1") (pin "4") (pinfunction "4_4") (pintype "passive"))
      (node (ref "U$1") (pin "VSS") (pinfunction "GND_VSS") (pintype "bidirectional"))
      (node (ref "U$2") (pin "DGND") (pinfunction "DGND_DGND") (pintype "output"))
      (node (ref "U$2") (pin "GND") (pinfunction "GND_GND") (pintype "power_in"))
      (node (ref "U$3") (pin "GND") (pinfunction "GND_GND") (pintype "bidirectional"))
      (node (ref "U$3") (pin "SND") (pinfunction "SGND_SND") (pintype "bidirectional"))
      (node (ref "U$4") (pin "15") (pinfunction "GND_15") (pintype "bidirectional"))
      (node (ref "U$4") (pin "23") (pinfunction "GND1_23") (pintype "bidirectional"))
      (node (ref "U$4") (pin "5") (pinfunction "UGND_5") (pintype "bidirectional"))
      (node (ref "U$6") (pin "GND1") (pinfunction "GND1_GND1") (pintype "input"))
      (node (ref "U$6") (pin "GND2") (pinfunction "GND2_GND2") (pintype "input"))
      (node (ref "X2") (pin "3") (pinfunction "S_3") (pintype "passive"))
      (node (ref "X4") (pin "5") (pinfunction "5_5") (pintype "passive"))
      (node (ref "X5") (pin "3") (pinfunction "S_3") (pintype "passive"))
    )
    (net (code "41") (name "Net-(3.3V-OK-PadA)") (class "Default")
      (node (ref "3.3V-OK") (pin "A") (pinfunction "A_A") (pintype "passive"))
      (node (ref "R27") (pin "1") (pinfunction "1_1") (pintype "passive"))
    )
    (net (code "42") (name "Net-(5V-OK-PadA)") (class "Default")
      (node (ref "5V-OK") (pin "A") (pinfunction "A_A") (pintype "passive"))
      (node (ref "RL4") (pin "2") (pinfunction "2_2") (pintype "passive"))
    )
    (net (code "43") (name "Net-(12V-OK-PadA)") (class "Default")
      (node (ref "12V-OK") (pin "A") (pinfunction "A_A") (pintype "passive"))
      (node (ref "RL3") (pin "1") (pinfunction "1_1") (pintype "passive"))
    )
    (net (code "44") (name "Net-(BLINK-PadA)") (class "Default")
      (node (ref "BLINK") (pin "A") (pinfunction "A_A") (pintype "passive"))
      (node (ref "RL5") (pin "2") (pinfunction "2_2") (pintype "passive"))
    )
    (net (code "45") (name "Net-(CFG-Pad4)") (class "Default")
      (node (ref "CFG") (pin "4") (pinfunction "4_4") (pintype "passive"))
      (node (ref "U$3") (pin "CFG") (pinfunction "CFG_CFG") (pintype "bidirectional"))
    )
    (net (code "46") (name "Net-(I/O1-2)") (class "Default")
      (node (ref "I/O1") (pin "PWM") (pinfunction "2_PWM") (pintype "bidirectional"))
      (node (ref "LED2") (pin "C") (pinfunction "C_C") (pintype "passive"))
      (node (ref "Q1") (pin "2") (pinfunction "D_2") (pintype "passive"))
    )
    (net (code "47") (name "Net-(I/O1-3)") (class "Default")
      (node (ref "I/O1") (pin "I/O") (pinfunction "3_I/O") (pintype "bidirectional"))
      (node (ref "R") (pin "2") (pinfunction "2_2") (pintype "passive"))
    )
    (net (code "48") (name "Net-(I/O2-2)") (class "Default")
      (node (ref "I/O2") (pin "PWM") (pinfunction "2_PWM") (pintype "bidirectional"))
      (node (ref "LED5") (pin "C") (pinfunction "C_C") (pintype "passive"))
      (node (ref "Q2") (pin "2") (pinfunction "D_2") (pintype "passive"))
    )
    (net (code "49") (name "Net-(I/O2-3)") (class "Default")
      (node (ref "I/O2") (pin "I/O") (pinfunction "3_I/O") (pintype "bidirectional"))
      (node (ref "R32") (pin "2") (pinfunction "2_2") (pintype "passive"))
    )
    (net (code "50") (name "Net-(I/O3-2)") (class "Default")
      (node (ref "I/O3") (pin "PWM") (pinfunction "2_PWM") (pintype "bidirectional"))
      (node (ref "LED6") (pin "C") (pinfunction "C_C") (pintype "passive"))
      (node (ref "Q4") (pin "2") (pinfunction "D_2") (pintype "passive"))
    )
    (net (code "51") (name "Net-(I/O3-3)") (class "Default")
      (node (ref "I/O3") (pin "I/O") (pinfunction "3_I/O") (pintype "bidirectional"))
      (node (ref "R33") (pin "2") (pinfunction "2_2") (pintype "passive"))
    )
    (net (code "52") (name "Net-(I/O4-2)") (class "Default")
      (node (ref "I/O4") (pin "PWM") (pinfunction "2_PWM") (pintype "bidirectional"))
      (node (ref "LED7") (pin "C") (pinfunction "C_C") (pintype "passive"))
      (node (ref "Q5") (pin "2") (pinfunction "D_2") (pintype "passive"))
    )
    (net (code "53") (name "Net-(I/O4-3)") (class "Default")
      (node (ref "I/O4") (pin "I/O") (pinfunction "3_I/O") (pintype "bidirectional"))
      (node (ref "R34") (pin "2") (pinfunction "2_2") (pintype "passive"))
    )
    (net (code "54") (name "Net-(I/O5-2)") (class "Default")
      (node (ref "I/O5") (pin "PWM") (pinfunction "2_PWM") (pintype "bidirectional"))
      (node (ref "LED8") (pin "C") (pinfunction "C_C") (pintype "passive"))
      (node (ref "Q6") (pin "2") (pinfunction "D_2") (pintype "passive"))
    )
    (net (code "55") (name "Net-(I/O5-3)") (class "Default")
      (node (ref "I/O5") (pin "I/O") (pinfunction "3_I/O") (pintype "bidirectional"))
      (node (ref "R35") (pin "2") (pinfunction "2_2") (pintype "passive"))
    )
    (net (code "56") (name "Net-(IC2-+)") (class "Default")
      (node (ref "C13") (pin "1") (pinfunction "1_1") (pintype "passive"))
      (node (ref "C14") (pin "2") (pinfunction "2_2") (pintype "passive"))
      (node (ref "IC2") (pin "3") (pinfunction "+_3") (pintype "input"))
      (node (ref "R19") (pin "1") (pinfunction "1_1") (pintype "passive"))
    )
    (net (code "57") (name "Net-(IC2--)") (class "Default")
      (node (ref "C13") (pin "2") (pinfunction "2_2") (pintype "passive"))
      (node (ref "C15") (pin "1") (pinfunction "1_1") (pintype "passive"))
      (node (ref "IC2") (pin "2") (pinfunction "-_2") (pintype "input"))
      (node (ref "R20") (pin "1") (pinfunction "1_1") (pintype "passive"))
    )
    (net (code "58") (name "Net-(IC2-OUT)") (class "Default")
      (node (ref "IC2") (pin "6") (pinfunction "OUT_6") (pintype "output"))
      (node (ref "R9") (pin "1") (pinfunction "1_1") (pintype "passive"))
    )
    (net (code "59") (name "Net-(IC2-RG-Pad1)") (class "Default")
      (node (ref "IC2") (pin "1") (pinfunction "RG_1") (pintype "passive"))
      (node (ref "R2") (pin "2") (pinfunction "2_2") (pintype "passive"))
    )
    (net (code "60") (name "Net-(IC2-RG-Pad8)") (class "Default")
      (node (ref "IC2") (pin "8") (pinfunction "RG_8") (pintype "passive"))
      (node (ref "R2") (pin "1") (pinfunction "1_1") (pintype "passive"))
    )
    (net (code "61") (name "Net-(J7B-S)") (class "Default")
      (node (ref "J7") (pin "2") (pinfunction "S_2") (pintype "passive"))
      (node (ref "Q7") (pin "2") (pinfunction "D_2") (pintype "passive"))
    )
    (net (code "62") (name "Net-(LED2-PadA)") (class "Default")
      (node (ref "LED2") (pin "A") (pinfunction "A_A") (pintype "passive"))
      (node (ref "R25") (pin "1") (pinfunction "1_1") (pintype "passive"))
    )
    (net (code "63") (name "Net-(LED5-PadA)") (class "Default")
      (node (ref "LED5") (pin "A") (pinfunction "A_A") (pintype "passive"))
      (node (ref "R4") (pin "1") (pinfunction "1_1") (pintype "passive"))
    )
    (net (code "64") (name "Net-(LED6-PadA)") (class "Default")
      (node (ref "LED6") (pin "A") (pinfunction "A_A") (pintype "passive"))
      (node (ref "R5") (pin "1") (pinfunction "1_1") (pintype "passive"))
    )
    (net (code "65") (name "Net-(LED7-PadA)") (class "Default")
      (node (ref "LED7") (pin "A") (pinfunction "A_A") (pintype "passive"))
      (node (ref "R6") (pin "1") (pinfunction "1_1") (pintype "passive"))
    )
    (net (code "66") (name "Net-(LED8-PadA)") (class "Default")
      (node (ref "LED8") (pin "A") (pinfunction "A_A") (pintype "passive"))
      (node (ref "R7") (pin "1") (pinfunction "1_1") (pintype "passive"))
    )
    (net (code "67") (name "Net-(LED9-PadA)") (class "Default")
      (node (ref "LED9") (pin "A") (pinfunction "A_A") (pintype "passive"))
      (node (ref "R12") (pin "1") (pinfunction "1_1") (pintype "passive"))
    )
    (net (code "68") (name "Net-(LED11-PadA)") (class "Default")
      (node (ref "LED11") (pin "A") (pinfunction "A_A") (pintype "passive"))
      (node (ref "R14") (pin "1") (pinfunction "1_1") (pintype "passive"))
    )
    (net (code "69") (name "Net-(LED11-PadC)") (class "Default")
      (node (ref "LED11") (pin "C") (pinfunction "C_C") (pintype "passive"))
      (node (ref "U$3") (pin "NET") (pinfunction "NET_NET") (pintype "bidirectional"))
    )
    (net (code "70") (name "Net-(LED12-PadA)") (class "Default")
      (node (ref "LED12") (pin "A") (pinfunction "A_A") (pintype "passive"))
      (node (ref "R39") (pin "1") (pinfunction "1_1") (pintype "passive"))
    )
    (net (code "71") (name "Net-(LED12-PadC)") (class "Default")
      (node (ref "LED12") (pin "C") (pinfunction "C_C") (pintype "passive"))
      (node (ref "U$3") (pin "ALM") (pinfunction "ALM_ALM") (pintype "bidirectional"))
    )
    (net (code "72") (name "Net-(Q7-G)") (class "Default")
      (node (ref "Q7") (pin "1") (pinfunction "G_1") (pintype "passive"))
      (node (ref "RL2") (pin "2") (pinfunction "2_2") (pintype "passive"))
    )
    (net (code "73") (name "Net-(R8-Pad2)") (class "Default")
      (node (ref "R8") (pin "2") (pinfunction "2_2") (pintype "passive"))
      (node (ref "U$3") (pin "TX1") (pinfunction "TX1_TX1") (pintype "bidirectional"))
    )
    (net (code "74") (name "Net-(R11-Pad2)") (class "Default")
      (node (ref "R11") (pin "2") (pinfunction "2_2") (pintype "passive"))
      (node (ref "U$3") (pin "RX1") (pinfunction "RX1_RX1") (pintype "bidirectional"))
    )
    (net (code "75") (name "Net-(R18-Pad2)") (class "Default")
      (node (ref "R18") (pin "2") (pinfunction "2_2") (pintype "passive"))
      (node (ref "U$1") (pin "SCK") (pinfunction "SCK_SCK") (pintype "bidirectional"))
    )
    (net (code "76") (name "Net-(R24-Pad2)") (class "Default")
      (node (ref "R24") (pin "2") (pinfunction "2_2") (pintype "passive"))
      (node (ref "X4") (pin "3") (pinfunction "3_3") (pintype "passive"))
    )
    (net (code "77") (name "Net-(R31-Pad2)") (class "Default")
      (node (ref "R31") (pin "2") (pinfunction "2_2") (pintype "passive"))
      (node (ref "X4") (pin "2") (pinfunction "2_2") (pintype "passive"))
    )
    (net (code "78") (name "Net-(U$1-CS)") (class "Default")
      (node (ref "R16") (pin "1") (pinfunction "1_1") (pintype "passive"))
      (node (ref "R17") (pin "1") (pinfunction "1_1") (pintype "passive"))
      (node (ref "U$1") (pin "CE") (pinfunction "CS_CE") (pintype "bidirectional"))
    )
    (net (code "79") (name "Net-(U$3-RNU)") (class "Default")
      (node (ref "LED9") (pin "C") (pinfunction "C_C") (pintype "passive"))
      (node (ref "U$3") (pin "RUN") (pinfunction "RNU_RUN") (pintype "bidirectional"))
    )
    (net (code "80") (name "Net-(U$4-AVCC)") (class "Default")
      (node (ref "C16") (pin "2") (pinfunction "2_2") (pintype "passive"))
      (node (ref "L1") (pin "1") (pinfunction "1_1") (pintype "passive"))
      (node (ref "U$4") (pin "24") (pinfunction "AVCC_24") (pintype "bidirectional"))
    )
    (net (code "81") (name "Net-(U$4-UCAP)") (class "Default")
      (node (ref "C3") (pin "2") (pinfunction "2_2") (pintype "passive"))
      (node (ref "U$4") (pin "6") (pinfunction "UCAP_6") (pintype "bidirectional"))
    )
    (net (code "82") (name "Net-(X1B-S)") (class "Default")
      (node (ref "R20") (pin "2") (pinfunction "2_2") (pintype "passive"))
      (node (ref "X1") (pin "2") (pinfunction "S_2") (pintype "passive"))
    )
    (net (code "83") (name "Net-(X1C-S)") (class "Default")
      (node (ref "R19") (pin "2") (pinfunction "2_2") (pintype "passive"))
      (node (ref "X1") (pin "3") (pinfunction "S_3") (pintype "passive"))
    )
    (net (code "84") (name "Net-(X2B-S)") (class "Default")
      (node (ref "R10") (pin "2") (pinfunction "2_2") (pintype "passive"))
      (node (ref "RL6") (pin "2") (pinfunction "2_2") (pintype "passive"))
      (node (ref "X2") (pin "2") (pinfunction "S_2") (pintype "passive"))
    )
    (net (code "85") (name "Net-(X5B-S)") (class "Default")
      (node (ref "R21") (pin "2") (pinfunction "2_2") (pintype "passive"))
      (node (ref "RL8") (pin "2") (pinfunction "2_2") (pintype "passive"))
      (node (ref "X5") (pin "2") (pinfunction "S_2") (pintype "passive"))
    )
    (net (code "86") (name "VUSB") (class "Default")
      (node (ref "C7") (pin "2") (pinfunction "2_2") (pintype "passive"))
      (node (ref "D4") (pin "A") (pinfunction "A_A") (pintype "passive"))
      (node (ref "U$4") (pin "7") (pinfunction "VBUS_7") (pintype "bidirectional"))
      (node (ref "X4") (pin "1") (pinfunction "1_1") (pintype "passive"))
    )
    (net (code "87") (name "unconnected-(CFG-Pad2)") (class "Default")
      (node (ref "CFG") (pin "2") (pinfunction "2_2") (pintype "passive"))
    )
    (net (code "88") (name "unconnected-(CFG-Pad3)") (class "Default")
      (node (ref "CFG") (pin "3") (pinfunction "3_3") (pintype "passive"))
    )
    (net (code "89") (name "unconnected-(Q1-D-Pad4)") (class "Default")
      (node (ref "Q1") (pin "4") (pinfunction "D_4") (pintype "passive"))
    )
    (net (code "90") (name "unconnected-(Q2-D-Pad4)") (class "Default")
      (node (ref "Q2") (pin "4") (pinfunction "D_4") (pintype "passive"))
    )
    (net (code "91") (name "unconnected-(Q4-D-Pad4)") (class "Default")
      (node (ref "Q4") (pin "4") (pinfunction "D_4") (pintype "passive"))
    )
    (net (code "92") (name "unconnected-(Q5-D-Pad4)") (class "Default")
      (node (ref "Q5") (pin "4") (pinfunction "D_4") (pintype "passive"))
    )
    (net (code "93") (name "unconnected-(Q6-D-Pad4)") (class "Default")
      (node (ref "Q6") (pin "4") (pinfunction "D_4") (pintype "passive"))
    )
    (net (code "94") (name "unconnected-(RESET1-Pad1)") (class "Default")
      (node (ref "RESET1") (pin "1") (pinfunction "1_1") (pintype "passive"))
    )
    (net (code "95") (name "unconnected-(RESET1-Pad3)") (class "Default")
      (node (ref "RESET1") (pin "3") (pinfunction "3_3") (pintype "passive"))
    )
    (net (code "96") (name "unconnected-(U$3-PadRST)") (class "Default")
      (node (ref "U$3") (pin "RST") (pinfunction "RST_RST") (pintype "bidirectional"))
    )
    (net (code "97") (name "unconnected-(X4-Pad4)") (class "Default")
      (node (ref "X4") (pin "4") (pinfunction "4_4") (pintype "passive"))
    )
  )
)
